# Connectors.net
KiCad netlist of a schematic drawn in Altium Designer
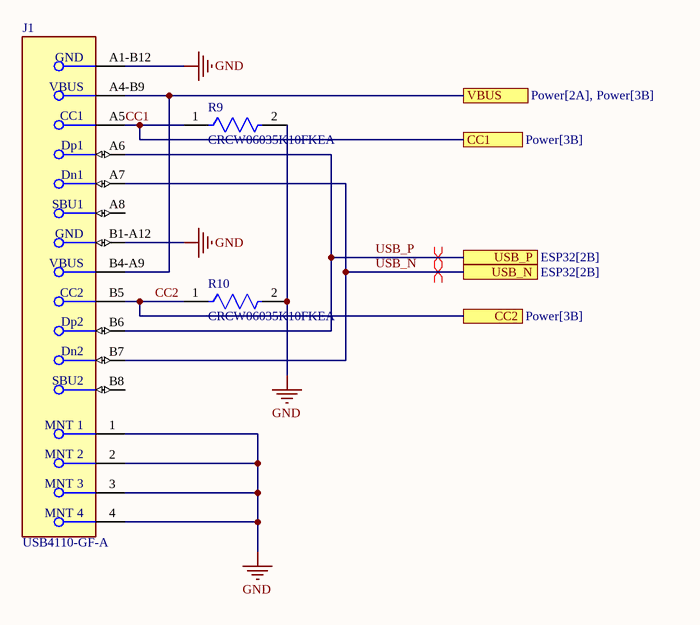
[diagram p0: Connectors.SchDoc]

(export (version "E")
  (design (tool "Eeschema 10.0.6"))
  (components
    (comp (ref "J1")
      (value "USB4110-GF-A")
      (footprint "FP-USB4110-GF-A-MFG")
      (description "CONN USB 2.0 TYPE-C R/A SMT")
      (fields
        (field (name "OCTOPART") "https://octopart.com/usb4110-gf-a-gct-103941985")
        (field (name "MANUFACTURER") "GCT")
      )
      (libsource (lib "Altium Content Vault") (part "e23f2b38bb3c3f98e683ebab9ede730"))
    )
    (comp (ref "R9")
      (value "CRCW06035K10FKEA")
      (footprint "FP-CRCW0603-e3-IPC_C")
      (description "RES Thick Film, 5.1kΩ, 1%, 0.1W, 100ppm/°C, 0603")
      (fields (field (name "TOLERANCE") "1%"))
      (libsource (lib "Altium Content Vault") (part "1029c3af85768c4190bb7ad29bc67b5"))
    )
    (comp (ref "R10")
      (value "CRCW06035K10FKEA")
      (footprint "FP-CRCW0603-e3-IPC_C")
      (description "RES Thick Film, 5.1kΩ, 1%, 0.1W, 100ppm/°C, 0603")
      (fields (field (name "TOLERANCE") "1%"))
      (libsource (lib "Altium Content Vault") (part "1029c3af85768c4190bb7ad29bc67b5"))
    )
  )
  (nets
    (net (code "1") (name "/CC1") (class "Default")
      (node (ref "J1") (pin "A5") (pinfunction "CC1_A5") (pintype "power_in"))
      (node (ref "R9") (pin "1") (pinfunction "1_1") (pintype "passive"))
    )
    (net (code "2") (name "/CC2") (class "Default")
      (node (ref "J1") (pin "B5") (pinfunction "CC2_B5") (pintype "power_in"))
      (node (ref "R10") (pin "1") (pinfunction "1_1") (pintype "passive"))
    )
    (net (code "3") (name "/USB_N") (class "Default")
      (node (ref "J1") (pin "A7") (pinfunction "Dn1_A7") (pintype "bidirectional"))
      (node (ref "J1") (pin "B7") (pinfunction "Dn2_B7") (pintype "bidirectional"))
    )
    (net (code "4") (name "/USB_P") (class "Default")
      (node (ref "J1") (pin "A6") (pinfunction "Dp1_A6") (pintype "bidirectional"))
      (node (ref "J1") (pin "B6") (pinfunction "Dp2_B6") (pintype "bidirectional"))
    )
    (net (code "5") (name "/VBUS") (class "Default")
      (node (ref "J1") (pin "A4-B9") (pinfunction "VBUS_A4-B9") (pintype "power_in"))
      (node (ref "J1") (pin "B4-A9") (pinfunction "VBUS_B4-A9") (pintype "power_in"))
    )
    (net (code "6") (name "GND") (class "Default")
      (node (ref "J1") (pin "1") (pinfunction "MNT_1_1") (pintype "passive"))
      (node (ref "J1") (pin "2") (pinfunction "MNT_2_2") (pintype "passive"))
      (node (ref "J1") (pin "3") (pinfunction "MNT_3_3") (pintype "passive"))
      (node (ref "J1") (pin "4") (pinfunction "MNT_4_4") (pintype "passive"))
      (node (ref "J1") (pin "A1-B12") (pinfunction "GND_A1-B12") (pintype "passive"))
      (node (ref "J1") (pin "B1-A12") (pinfunction "GND_B1-A12") (pintype "bidirectional"))
      (node (ref "R10") (pin "2") (pinfunction "2_2") (pintype "passive"))
      (node (ref "R9") (pin "2") (pinfunction "2_2") (pintype "passive"))
    )
    (net (code "7") (name "unconnected-(J1-SBU1-PadA8)") (class "Default")
      (node (ref "J1") (pin "A8") (pinfunction "SBU1_A8") (pintype "bidirectional"))
    )
    (net (code "8") (name "unconnected-(J1-SBU2-PadB8)") (class "Default")
      (node (ref "J1") (pin "B8") (pinfunction "SBU2_B8") (pintype "bidirectional"))
    )
  )
)
